# Joy2PS2.net
KiCad netlist of a schematic drawn in EAGLE
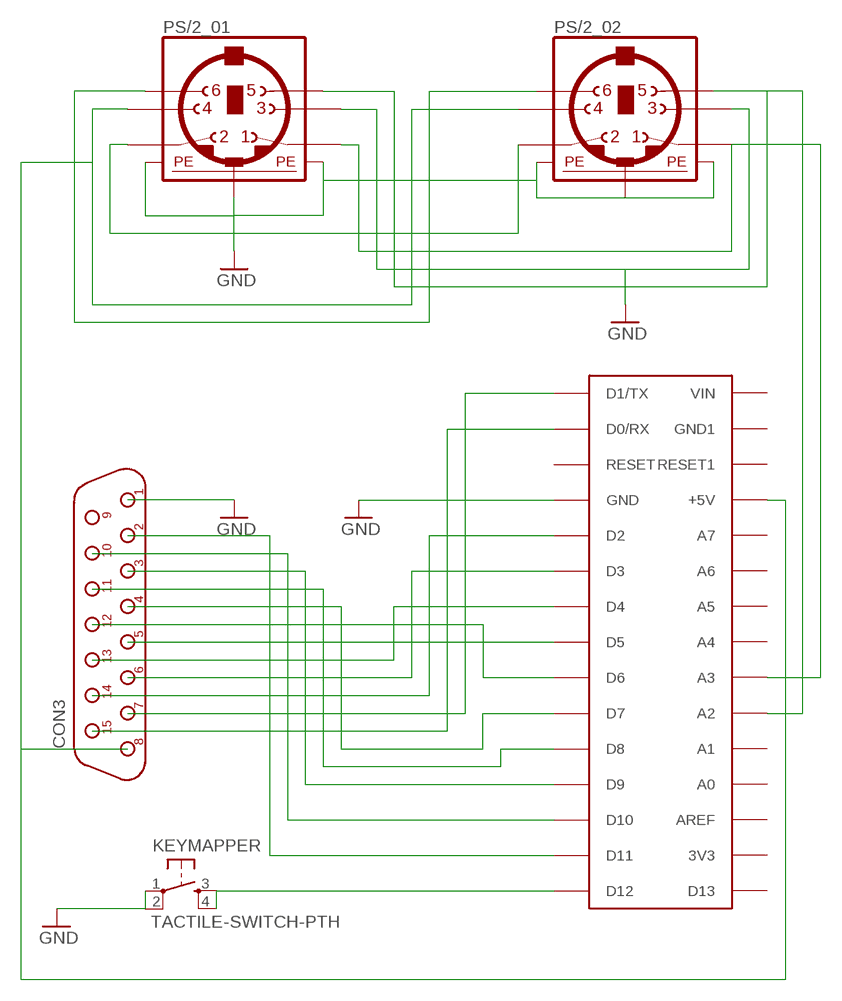
[diagram p0: schematic, sheet 1]

(export (version "E")
  (design (tool "Eeschema 10.0.6"))
  (components
    (comp (ref "ARDUINONANO")
      (value "ARDUINONANO")
      (footprint "eagle-import:PDIP-32")
      (libsource (lib "eagle-import") (part "ARDUINONANO"))
    )
    (comp (ref "CON3")
      (value "DB15F/90")
      (footprint "eagle-import:D-15F_90")
      (libsource (lib "eagle-import") (part "DB15F/90"))
    )
    (comp (ref "KEYMAPPER")
      (value "TACTILE-SWITCH-PTH")
      (footprint "eagle-import:TAC-SWITCH-PTH")
      (libsource (lib "eagle-import") (part "TACTILE-SWITCH-PTH"))
    )
    (comp (ref "PS/2_01")
      (value "MINI_DIN_6")
      (footprint "eagle-import:M_DIN6")
      (libsource (lib "eagle-import") (part "MINI_DIN_6"))
    )
    (comp (ref "PS/2_02")
      (value "MINI_DIN_6")
      (footprint "eagle-import:M_DIN6")
      (libsource (lib "eagle-import") (part "MINI_DIN_6"))
    )
  )
  (nets
    (net (code "1") (name "GND") (class "Default")
      (node (ref "ARDUINONANO") (pin "GND") (pinfunction "GND_GND") (pintype "bidirectional"))
      (node (ref "CON3") (pin "1") (pinfunction "1_1") (pintype "passive"))
      (node (ref "KEYMAPPER") (pin "1") (pinfunction "1_1") (pintype "passive"))
      (node (ref "KEYMAPPER") (pin "2") (pinfunction "2_2") (pintype "passive"))
      (node (ref "PS/2_01") (pin "3") (pinfunction "3_3") (pintype "passive"))
      (node (ref "PS/2_01") (pin "SH1") (pinfunction "PE1_SH1") (pintype "power_in"))
      (node (ref "PS/2_01") (pin "SH2") (pinfunction "PE2_SH2") (pintype "power_in"))
      (node (ref "PS/2_01") (pin "SH3") (pinfunction "PE3_SH3") (pintype "power_in"))
      (node (ref "PS/2_02") (pin "3") (pinfunction "3_3") (pintype "passive"))
      (node (ref "PS/2_02") (pin "SH1") (pinfunction "PE1_SH1") (pintype "power_in"))
      (node (ref "PS/2_02") (pin "SH2") (pinfunction "PE2_SH2") (pintype "power_in"))
      (node (ref "PS/2_02") (pin "SH3") (pinfunction "PE3_SH3") (pintype "power_in"))
    )
    (net (code "2") (name "Net-(ARDUINONANO-Pad+5V)") (class "Default")
      (node (ref "ARDUINONANO") (pin "+5V") (pinfunction "+5V_+5V") (pintype "bidirectional"))
      (node (ref "CON3") (pin "8") (pinfunction "8_8") (pintype "passive"))
      (node (ref "PS/2_01") (pin "4") (pinfunction "4_4") (pintype "passive"))
      (node (ref "PS/2_02") (pin "4") (pinfunction "4_4") (pintype "passive"))
    )
    (net (code "3") (name "Net-(ARDUINONANO-PadA2)") (class "Default")
      (node (ref "ARDUINONANO") (pin "A2") (pinfunction "A2_A2") (pintype "bidirectional"))
      (node (ref "PS/2_01") (pin "5") (pinfunction "5_5") (pintype "passive"))
      (node (ref "PS/2_02") (pin "5") (pinfunction "5_5") (pintype "passive"))
    )
    (net (code "4") (name "Net-(ARDUINONANO-PadA3)") (class "Default")
      (node (ref "ARDUINONANO") (pin "A3") (pinfunction "A3_A3") (pintype "bidirectional"))
      (node (ref "PS/2_01") (pin "1") (pinfunction "1_1") (pintype "passive"))
      (node (ref "PS/2_02") (pin "1") (pinfunction "1_1") (pintype "passive"))
    )
    (net (code "5") (name "Net-(ARDUINONANO-PadD0{slash}RX)") (class "Default")
      (node (ref "ARDUINONANO") (pin "D0/RX") (pinfunction "D0/RX_D0/RX") (pintype "bidirectional"))
      (node (ref "CON3") (pin "15") (pinfunction "15_15") (pintype "passive"))
    )
    (net (code "6") (name "Net-(ARDUINONANO-PadD1{slash}TX)") (class "Default")
      (node (ref "ARDUINONANO") (pin "D1/TX") (pinfunction "D1/TX_D1/TX") (pintype "bidirectional"))
      (node (ref "CON3") (pin "7") (pinfunction "7_7") (pintype "passive"))
    )
    (net (code "7") (name "Net-(ARDUINONANO-PadD2)") (class "Default")
      (node (ref "ARDUINONANO") (pin "D2") (pinfunction "D2_D2") (pintype "bidirectional"))
      (node (ref "CON3") (pin "14") (pinfunction "14_14") (pintype "passive"))
    )
    (net (code "8") (name "Net-(ARDUINONANO-PadD3)") (class "Default")
      (node (ref "ARDUINONANO") (pin "D3") (pinfunction "D3_D3") (pintype "bidirectional"))
      (node (ref "CON3") (pin "6") (pinfunction "6_6") (pintype "passive"))
    )
    (net (code "9") (name "Net-(ARDUINONANO-PadD4)") (class "Default")
      (node (ref "ARDUINONANO") (pin "D4") (pinfunction "D4_D4") (pintype "bidirectional"))
      (node (ref "CON3") (pin "13") (pinfunction "13_13") (pintype "passive"))
    )
    (net (code "10") (name "Net-(ARDUINONANO-PadD5)") (class "Default")
      (node (ref "ARDUINONANO") (pin "D5") (pinfunction "D5_D5") (pintype "bidirectional"))
      (node (ref "CON3") (pin "5") (pinfunction "5_5") (pintype "passive"))
    )
    (net (code "11") (name "Net-(ARDUINONANO-PadD6)") (class "Default")
      (node (ref "ARDUINONANO") (pin "D6") (pinfunction "D6_D6") (pintype "bidirectional"))
      (node (ref "CON3") (pin "12") (pinfunction "12_12") (pintype "passive"))
    )
    (net (code "12") (name "Net-(ARDUINONANO-PadD7)") (class "Default")
      (node (ref "ARDUINONANO") (pin "D7") (pinfunction "D7_D7") (pintype "bidirectional"))
      (node (ref "CON3") (pin "4") (pinfunction "4_4") (pintype "passive"))
    )
    (net (code "13") (name "Net-(ARDUINONANO-PadD8)") (class "Default")
      (node (ref "ARDUINONANO") (pin "D8") (pinfunction "D8_D8") (pintype "bidirectional"))
      (node (ref "CON3") (pin "11") (pinfunction "11_11") (pintype "passive"))
    )
    (net (code "14") (name "Net-(ARDUINONANO-PadD9)") (class "Default")
      (node (ref "ARDUINONANO") (pin "D9") (pinfunction "D9_D9") (pintype "bidirectional"))
      (node (ref "CON3") (pin "3") (pinfunction "3_3") (pintype "passive"))
    )
    (net (code "15") (name "Net-(ARDUINONANO-PadD10)") (class "Default")
      (node (ref "ARDUINONANO") (pin "D10") (pinfunction "D10_D10") (pintype "bidirectional"))
      (node (ref "CON3") (pin "10") (pinfunction "10_10") (pintype "passive"))
    )
    (net (code "16") (name "Net-(ARDUINONANO-PadD11)") (class "Default")
      (node (ref "ARDUINONANO") (pin "D11") (pinfunction "D11_D11") (pintype "bidirectional"))
      (node (ref "CON3") (pin "2") (pinfunction "2_2") (pintype "passive"))
    )
    (net (code "17") (name "Net-(ARDUINONANO-PadD12)") (class "Default")
      (node (ref "ARDUINONANO") (pin "D12") (pinfunction "D12_D12") (pintype "bidirectional"))
      (node (ref "KEYMAPPER") (pin "3") (pinfunction "3_3") (pintype "passive"))
      (node (ref "KEYMAPPER") (pin "4") (pinfunction "4_4") (pintype "passive"))
    )
    (net (code "18") (name "Net-(PS/2_01-Pad2)") (class "Default")
      (node (ref "PS/2_01") (pin "2") (pinfunction "2_2") (pintype "passive"))
      (node (ref "PS/2_02") (pin "2") (pinfunction "2_2") (pintype "passive"))
    )
    (net (code "19") (name "Net-(PS/2_01-Pad6)") (class "Default")
      (node (ref "PS/2_01") (pin "6") (pinfunction "6_6") (pintype "passive"))
      (node (ref "PS/2_02") (pin "6") (pinfunction "6_6") (pintype "passive"))
    )
    (net (code "20") (name "unconnected-(ARDUINONANO-Pad3V3)") (class "Default")
      (node (ref "ARDUINONANO") (pin "3V3") (pinfunction "3V3_3V3") (pintype "bidirectional"))
    )
    (net (code "21") (name "unconnected-(ARDUINONANO-PadA0)") (class "Default")
      (node (ref "ARDUINONANO") (pin "A0") (pinfunction "A0_A0") (pintype "bidirectional"))
    )
    (net (code "22") (name "unconnected-(ARDUINONANO-PadA1)") (class "Default")
      (node (ref "ARDUINONANO") (pin "A1") (pinfunction "A1_A1") (pintype "bidirectional"))
    )
    (net (code "23") (name "unconnected-(ARDUINONANO-PadA4)") (class "Default")
      (node (ref "ARDUINONANO") (pin "A4") (pinfunction "A4_A4") (pintype "bidirectional"))
    )
    (net (code "24") (name "unconnected-(ARDUINONANO-PadA5)") (class "Default")
      (node (ref "ARDUINONANO") (pin "A5") (pinfunction "A5_A5") (pintype "bidirectional"))
    )
    (net (code "25") (name "unconnected-(ARDUINONANO-PadA6)") (class "Default")
      (node (ref "ARDUINONANO") (pin "A6") (pinfunction "A6_A6") (pintype "bidirectional"))
    )
    (net (code "26") (name "unconnected-(ARDUINONANO-PadA7)") (class "Default")
      (node (ref "ARDUINONANO") (pin "A7") (pinfunction "A7_A7") (pintype "bidirectional"))
    )
    (net (code "27") (name "unconnected-(ARDUINONANO-PadAREF)") (class "Default")
      (node (ref "ARDUINONANO") (pin "AREF") (pinfunction "AREF_AREF") (pintype "bidirectional"))
    )
    (net (code "28") (name "unconnected-(ARDUINONANO-PadD13)") (class "Default")
      (node (ref "ARDUINONANO") (pin "D13") (pinfunction "D13_D13") (pintype "bidirectional"))
    )
    (net (code "29") (name "unconnected-(ARDUINONANO-PadGND1)") (class "Default")
      (node (ref "ARDUINONANO") (pin "GND1") (pinfunction "GND1_GND1") (pintype "bidirectional"))
    )
    (net (code "30") (name "unconnected-(ARDUINONANO-PadRESET)") (class "Default")
      (node (ref "ARDUINONANO") (pin "RESET") (pinfunction "RESET_RESET") (pintype "bidirectional"))
    )
    (net (code "31") (name "unconnected-(ARDUINONANO-PadRESET1)") (class "Default")
      (node (ref "ARDUINONANO") (pin "RESET1") (pinfunction "RESET1_RESET1") (pintype "bidirectional"))
    )
    (net (code "32") (name "unconnected-(ARDUINONANO-PadVIN)") (class "Default")
      (node (ref "ARDUINONANO") (pin "VIN") (pinfunction "VIN_VIN") (pintype "bidirectional"))
    )
    (net (code "33") (name "unconnected-(CON3-Pad9)") (class "Default")
      (node (ref "CON3") (pin "9") (pinfunction "9_9") (pintype "passive"))
    )
  )
)
